# Sheet1.net
KiCad netlist of a schematic drawn in Altium Designer
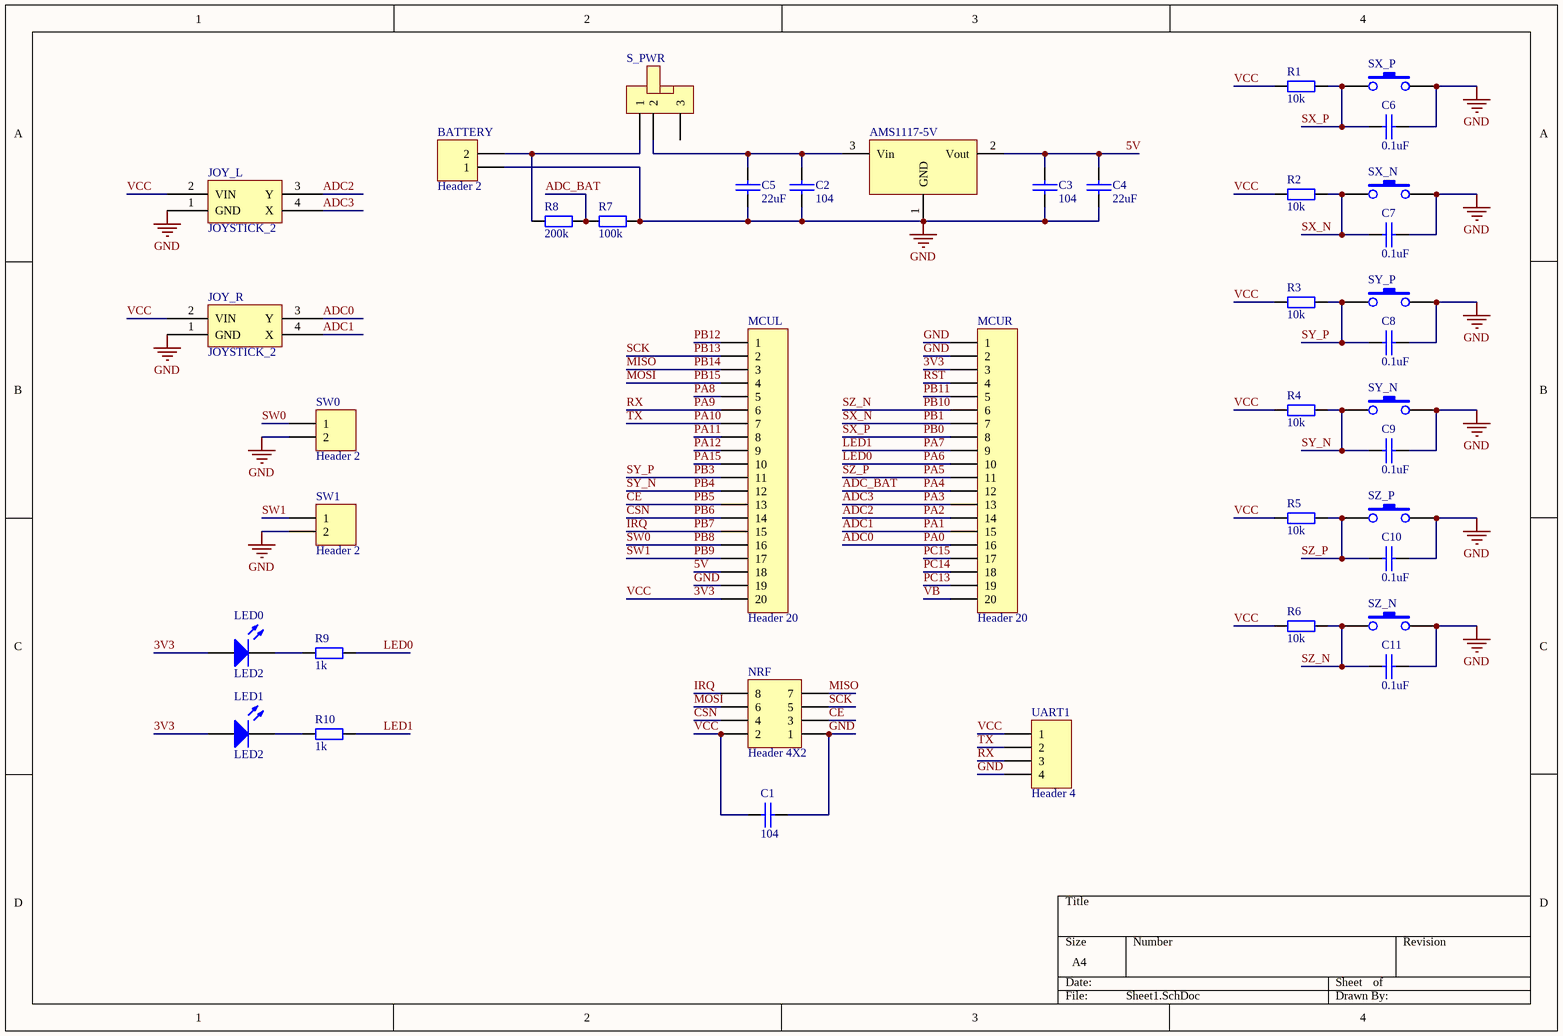
[diagram p0: Sheet1.SchDoc]

(export (version "E")
  (design (tool "Eeschema 10.0.6"))
  (components
    (comp (ref "AMS1117-5V")
      (value "AMS1117")
      (footprint "SOT-223")
      (description "2/4端口均输出3.3V")
      (libsource (lib "SkyWorks2") (part "AMS1117"))
    )
    (comp (ref "BATTERY")
      (value "Header 2")
      (footprint "HDR1X2")
      (description "Header, 2-Pin")
      (fields (field (name "PUBLISHER") "Altium Limited"))
      (libsource (lib "Miscellaneous Connectors") (part "Header 2"))
    )
    (comp (ref "C1")
      (value "104")
      (footprint "C1608[0603]N")
      (description "贴片无极性电容")
      (fields (field (name "Comment") "cap smd"))
      (libsource (lib "SkyWorks2") (part "CAP"))
    )
    (comp (ref "C2")
      (value "104")
      (footprint "C1608[0603]N")
      (description "贴片无极性电容")
      (fields (field (name "Comment") "cap smd"))
      (libsource (lib "SkyWorks2") (part "CAP"))
    )
    (comp (ref "C3")
      (value "104")
      (footprint "C1608[0603]N")
      (description "贴片无极性电容")
      (fields (field (name "Comment") "cap smd"))
      (libsource (lib "SkyWorks2") (part "CAP"))
    )
    (comp (ref "C4")
      (value "22uF")
      (footprint "C2012[0805]N")
      (description "贴片无极性电容")
      (fields (field (name "Comment") "cap smd"))
      (libsource (lib "SkyWorks2") (part "CAP"))
    )
    (comp (ref "C5")
      (value "22uF")
      (footprint "C2012[0805]N")
      (description "贴片无极性电容")
      (fields (field (name "Comment") "cap smd"))
      (libsource (lib "SkyWorks2") (part "CAP"))
    )
    (comp (ref "C6")
      (value "0.1uF")
      (footprint "C1608[0603]N")
      (description "贴片无极性电容")
      (fields (field (name "Comment") "cap smd"))
      (libsource (lib "SkyWorks2") (part "CAP"))
    )
    (comp (ref "C7")
      (value "0.1uF")
      (footprint "C1608[0603]N")
      (description "贴片无极性电容")
      (fields (field (name "Comment") "cap smd"))
      (libsource (lib "SkyWorks2") (part "CAP"))
    )
    (comp (ref "C8")
      (value "0.1uF")
      (footprint "C1608[0603]N")
      (description "贴片无极性电容")
      (fields (field (name "Comment") "cap smd"))
      (libsource (lib "SkyWorks2") (part "CAP"))
    )
    (comp (ref "C9")
      (value "0.1uF")
      (footprint "C1608[0603]N")
      (description "贴片无极性电容")
      (fields (field (name "Comment") "cap smd"))
      (libsource (lib "SkyWorks2") (part "CAP"))
    )
    (comp (ref "C10")
      (value "0.1uF")
      (footprint "C1608[0603]N")
      (description "贴片无极性电容")
      (fields (field (name "Comment") "cap smd"))
      (libsource (lib "SkyWorks2") (part "CAP"))
    )
    (comp (ref "C11")
      (value "0.1uF")
      (footprint "C1608[0603]N")
      (description "贴片无极性电容")
      (fields (field (name "Comment") "cap smd"))
      (libsource (lib "SkyWorks2") (part "CAP"))
    )
    (comp (ref "JOY_L")
      (value "JOYSTICK_2")
      (footprint "JOYSTICK_2")
      (libsource (lib "SkyWorks2") (part "JOYSTICK_2"))
    )
    (comp (ref "JOY_R")
      (value "JOYSTICK_2")
      (footprint "JOYSTICK_2")
      (libsource (lib "SkyWorks2") (part "JOYSTICK_2"))
    )
    (comp (ref "LED0")
      (value "LED2")
      (footprint "3.2X1.6X1.1")
      (description "Typical RED, GREEN, YELLOW, AMBER GaAs LED")
      (fields (field (name "PUBLISHER") "Altium Limited"))
      (libsource (lib "SkyWorks2") (part "LED2"))
    )
    (comp (ref "LED1")
      (value "LED2")
      (footprint "3.2X1.6X1.1")
      (description "Typical RED, GREEN, YELLOW, AMBER GaAs LED")
      (fields (field (name "PUBLISHER") "Altium Limited"))
      (libsource (lib "SkyWorks2") (part "LED2"))
    )
    (comp (ref "MCUL")
      (value "Header 20")
      (footprint "HDR1X20")
      (description "Header, 20-Pin")
      (fields (field (name "PUBLISHER") "Altium Limited"))
      (libsource (lib "Miscellaneous Connectors") (part "Header 20"))
    )
    (comp (ref "MCUR")
      (value "Header 20")
      (footprint "HDR1X20")
      (description "Header, 20-Pin")
      (fields (field (name "PUBLISHER") "Altium Limited"))
      (libsource (lib "Miscellaneous Connectors") (part "Header 20"))
    )
    (comp (ref "NRF")
      (value "Header 4X2")
      (footprint "HDR2X4")
      (description "Header, 4-Pin, Dual row")
      (fields (field (name "PUBLISHER") "Altium Limited"))
      (libsource (lib "Miscellaneous Connectors") (part "Header 4X2"))
    )
    (comp (ref "R1")
      (value "10k")
      (footprint "R1608[0603]")
      (fields (field (name "Comment") "RES1"))
      (libsource (lib "SkyWorks2") (part "RES1"))
    )
    (comp (ref "R2")
      (value "10k")
      (footprint "R1608[0603]")
      (fields (field (name "Comment") "RES1"))
      (libsource (lib "SkyWorks2") (part "RES1"))
    )
    (comp (ref "R3")
      (value "10k")
      (footprint "R1608[0603]")
      (fields (field (name "Comment") "RES1"))
      (libsource (lib "SkyWorks2") (part "RES1"))
    )
    (comp (ref "R4")
      (value "10k")
      (footprint "R1608[0603]")
      (fields (field (name "Comment") "RES1"))
      (libsource (lib "SkyWorks2") (part "RES1"))
    )
    (comp (ref "R5")
      (value "10k")
      (footprint "R1608[0603]")
      (fields (field (name "Comment") "RES1"))
      (libsource (lib "SkyWorks2") (part "RES1"))
    )
    (comp (ref "R6")
      (value "10k")
      (footprint "R1608[0603]")
      (fields (field (name "Comment") "RES1"))
      (libsource (lib "SkyWorks2") (part "RES1"))
    )
    (comp (ref "R7")
      (value "100k")
      (footprint "R1608[0603]")
      (fields (field (name "Comment") "RES1"))
      (libsource (lib "SkyWorks2") (part "RES1"))
    )
    (comp (ref "R8")
      (value "200k")
      (footprint "R1608[0603]")
      (fields (field (name "Comment") "RES1"))
      (libsource (lib "SkyWorks2") (part "RES1"))
    )
    (comp (ref "R9")
      (value "1k")
      (footprint "R1608[0603]")
      (fields (field (name "Comment") "RES1"))
      (libsource (lib "SkyWorks2") (part "RES1"))
    )
    (comp (ref "R10")
      (value "1k")
      (footprint "R1608[0603]")
      (fields (field (name "Comment") "RES1"))
      (libsource (lib "SkyWorks2") (part "RES1"))
    )
    (comp (ref "SW0")
      (value "Header 2")
      (footprint "HDR1X2")
      (description "Header, 2-Pin")
      (fields (field (name "PUBLISHER") "Altium Limited"))
      (libsource (lib "") (part "Header 2_1"))
    )
    (comp (ref "SW1")
      (value "Header 2")
      (footprint "HDR1X2")
      (description "Header, 2-Pin")
      (fields (field (name "PUBLISHER") "Altium Limited"))
      (libsource (lib "") (part "Header 2_1"))
    )
    (comp (ref "SX_N") (value "~") (footprint "SW") (libsource (lib "SkyWorks2") (part "SW")))
    (comp (ref "SX_P") (value "~") (footprint "SW") (libsource (lib "SkyWorks2") (part "SW")))
    (comp (ref "SY_N") (value "~") (footprint "SW") (libsource (lib "SkyWorks2") (part "SW")))
    (comp (ref "SY_P") (value "~") (footprint "SW") (libsource (lib "SkyWorks2") (part "SW")))
    (comp (ref "SZ_N") (value "~") (footprint "SW") (libsource (lib "SkyWorks2") (part "SW")))
    (comp (ref "SZ_P") (value "~") (footprint "SW") (libsource (lib "SkyWorks2") (part "SW")))
    (comp (ref "S_PWR")
      (value "3脚拨动开关侧")
      (footprint "3脚拨动开关侧")
      (libsource (lib "SkyWorks2") (part "3脚拨动开关侧"))
    )
    (comp (ref "UART1")
      (value "Header 4")
      (footprint "HDR1X4")
      (description "Header, 4-Pin")
      (fields (field (name "PUBLISHER") "Altium Limited"))
      (libsource (lib "Miscellaneous Connectors") (part "Header 4"))
    )
  )
  (nets
    (net (code "1") (name "/3V3") (class "Default")
      (node (ref "C1") (pin "1") (pinfunction "1_1") (pintype "passive"))
      (node (ref "JOY_L") (pin "2") (pinfunction "VIN_2") (pintype "passive"))
      (node (ref "JOY_R") (pin "2") (pinfunction "VIN_2") (pintype "passive"))
      (node (ref "LED0") (pin "1") (pinfunction "A_1") (pintype "passive"))
      (node (ref "LED1") (pin "1") (pinfunction "A_1") (pintype "passive"))
      (node (ref "MCUL") (pin "20") (pinfunction "20_20") (pintype "passive"))
      (node (ref "MCUR") (pin "3") (pinfunction "3_3") (pintype "passive"))
      (node (ref "NRF") (pin "2") (pinfunction "2_2") (pintype "passive"))
      (node (ref "R1") (pin "2") (pinfunction "2_2") (pintype "passive"))
      (node (ref "R2") (pin "2") (pinfunction "2_2") (pintype "passive"))
      (node (ref "R3") (pin "2") (pinfunction "2_2") (pintype "passive"))
      (node (ref "R4") (pin "2") (pinfunction "2_2") (pintype "passive"))
      (node (ref "R5") (pin "2") (pinfunction "2_2") (pintype "passive"))
      (node (ref "R6") (pin "2") (pinfunction "2_2") (pintype "passive"))
      (node (ref "UART1") (pin "1") (pinfunction "1_1") (pintype "passive"))
    )
    (net (code "2") (name "/5V") (class "Default")
      (node (ref "AMS1117-5V") (pin "2") (pinfunction "Vout_2") (pintype "passive"))
      (node (ref "C3") (pin "1") (pinfunction "1_1") (pintype "passive"))
      (node (ref "C4") (pin "1") (pinfunction "1_1") (pintype "passive"))
      (node (ref "MCUL") (pin "18") (pinfunction "18_18") (pintype "passive"))
    )
    (net (code "3") (name "/ADC0") (class "Default")
      (node (ref "JOY_R") (pin "3") (pinfunction "Y_3") (pintype "passive"))
      (node (ref "MCUR") (pin "16") (pinfunction "16_16") (pintype "passive"))
    )
    (net (code "4") (name "/ADC1") (class "Default")
      (node (ref "JOY_R") (pin "4") (pinfunction "X_4") (pintype "passive"))
      (node (ref "MCUR") (pin "15") (pinfunction "15_15") (pintype "passive"))
    )
    (net (code "5") (name "/ADC2") (class "Default")
      (node (ref "JOY_L") (pin "3") (pinfunction "Y_3") (pintype "passive"))
      (node (ref "MCUR") (pin "14") (pinfunction "14_14") (pintype "passive"))
    )
    (net (code "6") (name "/ADC3") (class "Default")
      (node (ref "JOY_L") (pin "4") (pinfunction "X_4") (pintype "passive"))
      (node (ref "MCUR") (pin "13") (pinfunction "13_13") (pintype "passive"))
    )
    (net (code "7") (name "/ADC_BAT") (class "Default")
      (node (ref "MCUR") (pin "12") (pinfunction "12_12") (pintype "passive"))
      (node (ref "R7") (pin "2") (pinfunction "2_2") (pintype "passive"))
      (node (ref "R8") (pin "1") (pinfunction "1_1") (pintype "passive"))
    )
    (net (code "8") (name "/CE") (class "Default")
      (node (ref "MCUL") (pin "13") (pinfunction "13_13") (pintype "passive"))
      (node (ref "NRF") (pin "3") (pinfunction "3_3") (pintype "passive"))
    )
    (net (code "9") (name "/CSN") (class "Default")
      (node (ref "MCUL") (pin "14") (pinfunction "14_14") (pintype "passive"))
      (node (ref "NRF") (pin "4") (pinfunction "4_4") (pintype "passive"))
    )
    (net (code "10") (name "/IRQ") (class "Default")
      (node (ref "MCUL") (pin "15") (pinfunction "15_15") (pintype "passive"))
      (node (ref "NRF") (pin "8") (pinfunction "8_8") (pintype "passive"))
    )
    (net (code "11") (name "/LED0") (class "Default")
      (node (ref "MCUR") (pin "10") (pinfunction "10_10") (pintype "passive"))
      (node (ref "R9") (pin "1") (pinfunction "1_1") (pintype "passive"))
    )
    (net (code "12") (name "/LED1") (class "Default")
      (node (ref "MCUR") (pin "9") (pinfunction "9_9") (pintype "passive"))
      (node (ref "R10") (pin "1") (pinfunction "1_1") (pintype "passive"))
    )
    (net (code "13") (name "/MISO") (class "Default")
      (node (ref "MCUL") (pin "3") (pinfunction "3_3") (pintype "passive"))
      (node (ref "NRF") (pin "7") (pinfunction "7_7") (pintype "passive"))
    )
    (net (code "14") (name "/MOSI") (class "Default")
      (node (ref "MCUL") (pin "4") (pinfunction "4_4") (pintype "passive"))
      (node (ref "NRF") (pin "6") (pinfunction "6_6") (pintype "passive"))
    )
    (net (code "15") (name "/PA5") (class "Default")
      (node (ref "C10") (pin "1") (pinfunction "1_1") (pintype "passive"))
      (node (ref "MCUR") (pin "11") (pinfunction "11_11") (pintype "passive"))
      (node (ref "R5") (pin "1") (pinfunction "1_1") (pintype "passive"))
      (node (ref "SZ_P") (pin "1") (pinfunction "1_1") (pintype "passive"))
    )
    (net (code "16") (name "/PA8") (class "Default")
      (node (ref "MCUL") (pin "5") (pinfunction "5_5") (pintype "passive"))
    )
    (net (code "17") (name "/PA9") (class "Default")
      (node (ref "MCUL") (pin "6") (pinfunction "6_6") (pintype "passive"))
      (node (ref "UART1") (pin "3") (pinfunction "3_3") (pintype "passive"))
    )
    (net (code "18") (name "/PA10") (class "Default")
      (node (ref "MCUL") (pin "7") (pinfunction "7_7") (pintype "passive"))
      (node (ref "UART1") (pin "2") (pinfunction "2_2") (pintype "passive"))
    )
    (net (code "19") (name "/PA11") (class "Default")
      (node (ref "MCUL") (pin "8") (pinfunction "8_8") (pintype "passive"))
    )
    (net (code "20") (name "/PA12") (class "Default")
      (node (ref "MCUL") (pin "9") (pinfunction "9_9") (pintype "passive"))
    )
    (net (code "21") (name "/PA15") (class "Default")
      (node (ref "MCUL") (pin "10") (pinfunction "10_10") (pintype "passive"))
    )
    (net (code "22") (name "/PB0") (class "Default")
      (node (ref "C6") (pin "1") (pinfunction "1_1") (pintype "passive"))
      (node (ref "MCUR") (pin "8") (pinfunction "8_8") (pintype "passive"))
      (node (ref "R1") (pin "1") (pinfunction "1_1") (pintype "passive"))
      (node (ref "SX_P") (pin "1") (pinfunction "1_1") (pintype "passive"))
    )
    (net (code "23") (name "/PB1") (class "Default")
      (node (ref "C7") (pin "1") (pinfunction "1_1") (pintype "passive"))
      (node (ref "MCUR") (pin "7") (pinfunction "7_7") (pintype "passive"))
      (node (ref "R2") (pin "1") (pinfunction "1_1") (pintype "passive"))
      (node (ref "SX_N") (pin "1") (pinfunction "1_1") (pintype "passive"))
    )
    (net (code "24") (name "/PB3") (class "Default")
      (node (ref "C8") (pin "1") (pinfunction "1_1") (pintype "passive"))
      (node (ref "MCUL") (pin "11") (pinfunction "11_11") (pintype "passive"))
      (node (ref "R3") (pin "1") (pinfunction "1_1") (pintype "passive"))
      (node (ref "SY_P") (pin "1") (pinfunction "1_1") (pintype "passive"))
    )
    (net (code "25") (name "/PB4") (class "Default")
      (node (ref "C9") (pin "1") (pinfunction "1_1") (pintype "passive"))
      (node (ref "MCUL") (pin "12") (pinfunction "12_12") (pintype "passive"))
      (node (ref "R4") (pin "1") (pinfunction "1_1") (pintype "passive"))
      (node (ref "SY_N") (pin "1") (pinfunction "1_1") (pintype "passive"))
    )
    (net (code "26") (name "/PB8") (class "Default")
      (node (ref "MCUL") (pin "16") (pinfunction "16_16") (pintype "passive"))
      (node (ref "SW0") (pin "1") (pinfunction "1_1") (pintype "passive"))
    )
    (net (code "27") (name "/PB9") (class "Default")
      (node (ref "MCUL") (pin "17") (pinfunction "17_17") (pintype "passive"))
      (node (ref "SW1") (pin "1") (pinfunction "1_1") (pintype "passive"))
    )
    (net (code "28") (name "/PB10") (class "Default")
      (node (ref "C11") (pin "1") (pinfunction "1_1") (pintype "passive"))
      (node (ref "MCUR") (pin "6") (pinfunction "6_6") (pintype "passive"))
      (node (ref "R6") (pin "1") (pinfunction "1_1") (pintype "passive"))
      (node (ref "SZ_N") (pin "1") (pinfunction "1_1") (pintype "passive"))
    )
    (net (code "29") (name "/PB11") (class "Default")
      (node (ref "MCUR") (pin "5") (pinfunction "5_5") (pintype "passive"))
    )
    (net (code "30") (name "/PB12") (class "Default")
      (node (ref "MCUL") (pin "1") (pinfunction "1_1") (pintype "passive"))
    )
    (net (code "31") (name "/PB13") (class "Default")
      (node (ref "MCUL") (pin "2") (pinfunction "2_2") (pintype "passive"))
      (node (ref "NRF") (pin "5") (pinfunction "5_5") (pintype "passive"))
    )
    (net (code "32") (name "/PC13") (class "Default")
      (node (ref "MCUR") (pin "19") (pinfunction "19_19") (pintype "passive"))
    )
    (net (code "33") (name "/PC14") (class "Default")
      (node (ref "MCUR") (pin "18") (pinfunction "18_18") (pintype "passive"))
    )
    (net (code "34") (name "/PC15") (class "Default")
      (node (ref "MCUR") (pin "17") (pinfunction "17_17") (pintype "passive"))
    )
    (net (code "35") (name "/RST") (class "Default")
      (node (ref "MCUR") (pin "4") (pinfunction "4_4") (pintype "passive"))
    )
    (net (code "36") (name "/VB") (class "Default")
      (node (ref "MCUR") (pin "20") (pinfunction "20_20") (pintype "passive"))
    )
    (net (code "37") (name "GND") (class "Default")
      (node (ref "AMS1117-5V") (pin "1") (pinfunction "GND_1") (pintype "passive"))
      (node (ref "BATTERY") (pin "1") (pinfunction "1_1") (pintype "passive"))
      (node (ref "C1") (pin "2") (pinfunction "2_2") (pintype "passive"))
      (node (ref "C10") (pin "2") (pinfunction "2_2") (pintype "passive"))
      (node (ref "C11") (pin "2") (pinfunction "2_2") (pintype "passive"))
      (node (ref "C2") (pin "2") (pinfunction "2_2") (pintype "passive"))
      (node (ref "C3") (pin "2") (pinfunction "2_2") (pintype "passive"))
      (node (ref "C4") (pin "2") (pinfunction "2_2") (pintype "passive"))
      (node (ref "C5") (pin "2") (pinfunction "2_2") (pintype "passive"))
      (node (ref "C6") (pin "2") (pinfunction "2_2") (pintype "passive"))
      (node (ref "C7") (pin "2") (pinfunction "2_2") (pintype "passive"))
      (node (ref "C8") (pin "2") (pinfunction "2_2") (pintype "passive"))
      (node (ref "C9") (pin "2") (pinfunction "2_2") (pintype "passive"))
      (node (ref "JOY_L") (pin "1") (pinfunction "GND_1") (pintype "passive"))
      (node (ref "JOY_R") (pin "1") (pinfunction "GND_1") (pintype "passive"))
      (node (ref "MCUL") (pin "19") (pinfunction "19_19") (pintype "passive"))
      (node (ref "MCUR") (pin "1") (pinfunction "1_1") (pintype "passive"))
      (node (ref "MCUR") (pin "2") (pinfunction "2_2") (pintype "passive"))
      (node (ref "NRF") (pin "1") (pinfunction "1_1") (pintype "passive"))
      (node (ref "R7") (pin "1") (pinfunction "1_1") (pintype "passive"))
      (node (ref "SW0") (pin "2") (pinfunction "2_2") (pintype "passive"))
      (node (ref "SW1") (pin "2") (pinfunction "2_2") (pintype "passive"))
      (node (ref "SX_N") (pin "2") (pinfunction "2_2") (pintype "passive"))
      (node (ref "SX_P") (pin "2") (pinfunction "2_2") (pintype "passive"))
      (node (ref "SY_N") (pin "2") (pinfunction "2_2") (pintype "passive"))
      (node (ref "SY_P") (pin "2") (pinfunction "2_2") (pintype "passive"))
      (node (ref "SZ_N") (pin "2") (pinfunction "2_2") (pintype "passive"))
      (node (ref "SZ_P") (pin "2") (pinfunction "2_2") (pintype "passive"))
      (node (ref "UART1") (pin "4") (pinfunction "4_4") (pintype "passive"))
    )
    (net (code "38") (name "Net-(AMS1117-5V-Vin)") (class "Default")
      (node (ref "AMS1117-5V") (pin "3") (pinfunction "Vin_3") (pintype "passive"))
      (node (ref "C2") (pin "1") (pinfunction "1_1") (pintype "passive"))
      (node (ref "C5") (pin "1") (pinfunction "1_1") (pintype "passive"))
      (node (ref "S_PWR") (pin "2") (pinfunction "2_2") (pintype "passive"))
    )
    (net (code "39") (name "Net-(BATTERY-Pad2)") (class "Default")
      (node (ref "BATTERY") (pin "2") (pinfunction "2_2") (pintype "passive"))
      (node (ref "R8") (pin "2") (pinfunction "2_2") (pintype "passive"))
      (node (ref "S_PWR") (pin "1") (pinfunction "1_1") (pintype "passive"))
    )
    (net (code "40") (name "Net-(LED0-K)") (class "Default")
      (node (ref "LED0") (pin "2") (pinfunction "K_2") (pintype "passive"))
      (node (ref "R9") (pin "2") (pinfunction "2_2") (pintype "passive"))
    )
    (net (code "41") (name "Net-(LED1-K)") (class "Default")
      (node (ref "LED1") (pin "2") (pinfunction "K_2") (pintype "passive"))
      (node (ref "R10") (pin "2") (pinfunction "2_2") (pintype "passive"))
    )
    (net (code "42") (name "unconnected-(S_PWR-Pad3)") (class "Default")
      (node (ref "S_PWR") (pin "3") (pinfunction "3_3") (pintype "passive"))
    )
  )
)
